# VREG_AOZ1284PI_3V8_4A.net
KiCad netlist of a schematic drawn in Altium Designer
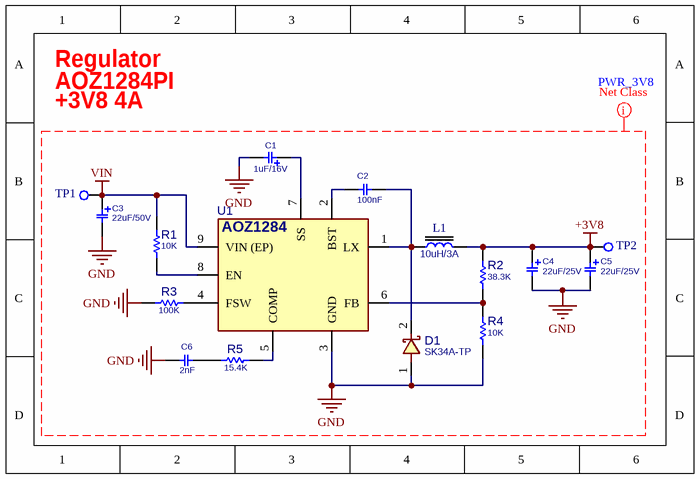
[diagram p0: VREG AOZ1284PI +3V8 4A.SchDoc]

(export (version "E")
  (design (tool "Eeschema 10.0.6"))
  (components
    (comp (ref "C1")
      (value "1uF/16V")
      (footprint "C_TN_A")
      (description "CAP, SMD, TAN")
      (libsource (lib "Passive") (part "CAP_SMD_TAN"))
    )
    (comp (ref "C2")
      (value "100nF")
      (footprint "C0603S")
      (description "CAP, SMD, MLCC")
      (fields (field (name "MANF_P#") "MANF_PART#") (field (name "MANF") "Murata"))
      (libsource (lib "Passive") (part "CAP_SMD_MLCC"))
    )
    (comp (ref "C3")
      (value "22uF/50V")
      (footprint "C_TN_A")
      (description "CAP, SMD, TAN")
      (libsource (lib "Passive") (part "CAP_SMD_TAN"))
    )
    (comp (ref "C4")
      (value "22uF/25V")
      (footprint "C_TN_A")
      (description "CAP, SMD, TAN")
      (libsource (lib "Passive") (part "CAP_SMD_TAN"))
    )
    (comp (ref "C5")
      (value "22uF/25V")
      (footprint "C_TN_A")
      (description "CAP, SMD, TAN")
      (libsource (lib "Passive") (part "CAP_SMD_TAN"))
    )
    (comp (ref "C6")
      (value "2nF")
      (footprint "C0603S")
      (description "CAP, SMD, MLCC")
      (fields (field (name "MANF_P#") "MANF_PART#") (field (name "MANF") "Murata"))
      (libsource (lib "Passive") (part "CAP_SMD_MLCC"))
    )
    (comp (ref "D1")
      (value "SK34A-TP")
      (footprint "D_SMA")
      (description "DIODE, SCHOTTKY, 40V, 3A")
      (fields (field (name "MANF") "Vishay") (field (name "MANF_P#") "SS14-E3"))
      (libsource (lib "PW Components 97_492") (part "DIODE_SMD_SCHOTTKY_SK34A-TP"))
    )
    (comp (ref "L1")
      (value "10uH/3A")
      (footprint "L_8X8")
      (description "IND, PWR, SMD")
      (libsource (lib "Passive") (part "INDPWR_SMD"))
    )
    (comp (ref "R1")
      (value "10K")
      (footprint "R0603S")
      (description "RES, SMD")
      (fields (field (name "MANF_P#") "RK73H1ETTP4701F") (field (name "MANF") "KOA SPEER"))
      (libsource (lib "Passive") (part "RES_SMD"))
    )
    (comp (ref "R2")
      (value "38.3K")
      (footprint "R0603S")
      (description "RES, SMD")
      (fields (field (name "MANF_P#") "RK73H1ETTP4701F") (field (name "MANF") "KOA SPEER"))
      (libsource (lib "Passive") (part "RES_SMD"))
    )
    (comp (ref "R3")
      (value "100K")
      (footprint "R0603S")
      (description "RES, SMD")
      (fields (field (name "MANF_P#") "RK73H1ETTP4701F") (field (name "MANF") "KOA SPEER"))
      (libsource (lib "Passive") (part "RES_SMD"))
    )
    (comp (ref "R4")
      (value "10K")
      (footprint "R0603S")
      (description "RES, SMD")
      (fields (field (name "MANF_P#") "RK73H1ETTP4701F") (field (name "MANF") "KOA SPEER"))
      (libsource (lib "Passive") (part "RES_SMD"))
    )
    (comp (ref "R5")
      (value "15.4K")
      (footprint "R0603S")
      (description "RES, SMD")
      (fields (field (name "MANF_P#") "RK73H1ETTP4701F") (field (name "MANF") "KOA SPEER"))
      (libsource (lib "Passive") (part "RES_SMD"))
    )
    (comp (ref "TP1")
      (value "Test Point")
      (footprint "TPSMD_C1")
      (libsource (lib "PW Components") (part "Test Point"))
    )
    (comp (ref "TP2")
      (value "Test Point")
      (footprint "TPSMD_C1")
      (libsource (lib "PW Components") (part "Test Point"))
    )
    (comp (ref "U1")
      (value "AOZ1021AI")
      (footprint "SO_8T")
      (description "REG, Switching, Buck, 4A, ADJ, 500KHz, 3~36VIN, SO-8")
      (fields (field (name "MANF") "AOSMD"))
      (libsource (lib "PW Components 97_492") (part "VREG_AOZ1284PI_SO8"))
    )
  )
  (nets
    (net (code "1") (name "+3V8") (class "Default")
      (node (ref "C4") (pin "1") (pinfunction "1_1") (pintype "passive"))
      (node (ref "C5") (pin "1") (pinfunction "1_1") (pintype "passive"))
      (node (ref "L1") (pin "2") (pinfunction "2_2") (pintype "passive"))
      (node (ref "R2") (pin "1") (pinfunction "1_1") (pintype "passive"))
      (node (ref "TP2") (pin "1") (pinfunction "TP_1") (pintype "passive"))
    )
    (net (code "2") (name "GND") (class "Default")
      (node (ref "C1") (pin "2") (pinfunction "2_2") (pintype "passive"))
      (node (ref "C3") (pin "2") (pinfunction "2_2") (pintype "passive"))
      (node (ref "C4") (pin "2") (pinfunction "2_2") (pintype "passive"))
      (node (ref "C5") (pin "2") (pinfunction "2_2") (pintype "passive"))
      (node (ref "C6") (pin "2") (pinfunction "2_2") (pintype "passive"))
      (node (ref "D1") (pin "1") (pinfunction "1_1") (pintype "passive"))
      (node (ref "R3") (pin "1") (pinfunction "1_1") (pintype "passive"))
      (node (ref "R4") (pin "2") (pinfunction "2_2") (pintype "passive"))
      (node (ref "U1") (pin "3") (pinfunction "GND_3") (pintype "power_in"))
    )
    (net (code "3") (name "Net-(C6-Pad1)") (class "Default")
      (node (ref "C6") (pin "1") (pinfunction "1_1") (pintype "passive"))
      (node (ref "R5") (pin "1") (pinfunction "1_1") (pintype "passive"))
    )
    (net (code "4") (name "Net-(U1-BST)") (class "Default")
      (node (ref "C2") (pin "2") (pinfunction "2_2") (pintype "passive"))
      (node (ref "U1") (pin "2") (pinfunction "BST_2") (pintype "passive"))
    )
    (net (code "5") (name "Net-(U1-COMP)") (class "Default")
      (node (ref "R5") (pin "2") (pinfunction "2_2") (pintype "passive"))
      (node (ref "U1") (pin "5") (pinfunction "COMP_5") (pintype "power_in"))
    )
    (net (code "6") (name "Net-(U1-EN)") (class "Default")
      (node (ref "R1") (pin "2") (pinfunction "2_2") (pintype "passive"))
      (node (ref "U1") (pin "8") (pinfunction "EN_8") (pintype "passive"))
    )
    (net (code "7") (name "Net-(U1-FB)") (class "Default")
      (node (ref "R2") (pin "2") (pinfunction "2_2") (pintype "passive"))
      (node (ref "R4") (pin "1") (pinfunction "1_1") (pintype "passive"))
      (node (ref "U1") (pin "6") (pinfunction "FB_6") (pintype "passive"))
    )
    (net (code "8") (name "Net-(U1-FSW)") (class "Default")
      (node (ref "R3") (pin "2") (pinfunction "2_2") (pintype "passive"))
      (node (ref "U1") (pin "4") (pinfunction "FSW_4") (pintype "passive"))
    )
    (net (code "9") (name "Net-(U1-LX)") (class "Default")
      (node (ref "C2") (pin "1") (pinfunction "1_1") (pintype "passive"))
      (node (ref "D1") (pin "2") (pinfunction "2_2") (pintype "passive"))
      (node (ref "L1") (pin "1") (pinfunction "1_1") (pintype "passive"))
      (node (ref "U1") (pin "1") (pinfunction "LX_1") (pintype "passive"))
    )
    (net (code "10") (name "Net-(U1-SS)") (class "Default")
      (node (ref "C1") (pin "1") (pinfunction "1_1") (pintype "passive"))
      (node (ref "U1") (pin "7") (pinfunction "SS_7") (pintype "passive"))
    )
    (net (code "11") (name "VIN") (class "Default")
      (node (ref "C3") (pin "1") (pinfunction "1_1") (pintype "passive"))
      (node (ref "R1") (pin "1") (pinfunction "1_1") (pintype "passive"))
      (node (ref "TP1") (pin "1") (pinfunction "TP_1") (pintype "passive"))
      (node (ref "U1") (pin "9") (pinfunction "VIN_(EP)_9") (pintype "power_in"))
    )
  )
)
